# Relay.net
KiCad netlist of a schematic drawn in Altium Designer
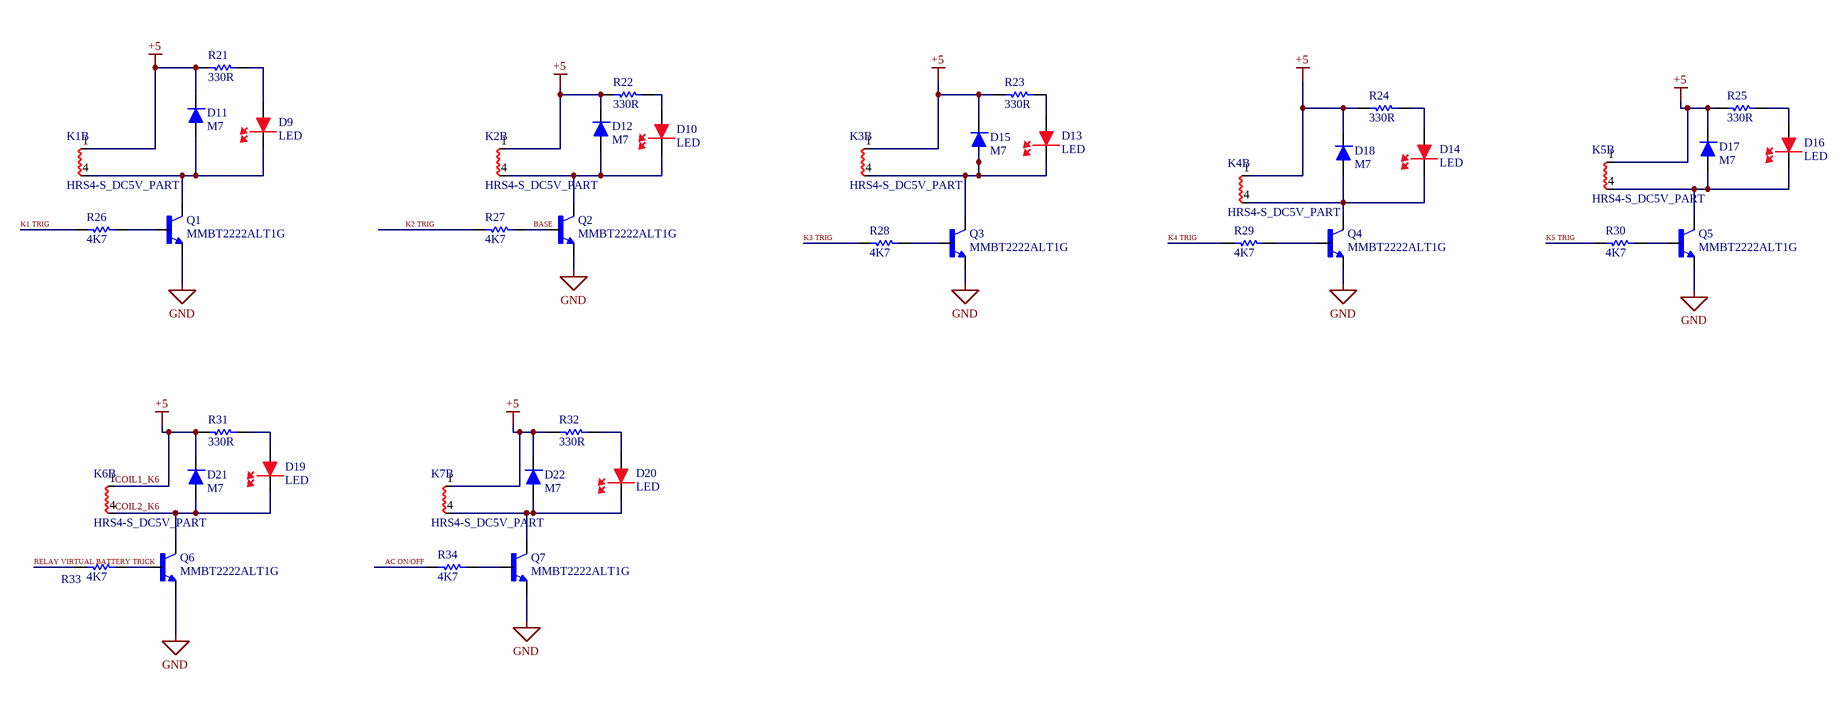
[diagram p0: Relay.SchDoc]

(export (version "E")
  (design (tool "Eeschema 10.0.6"))
  (components
    (comp (ref "D9")
      (value "LED")
      (footprint "0805 (1205) LED")
      (description "LED SMD  mcd,Red Color Red Diffused Lens")
      (libsource (lib "PCB_Project_1") (part "LED RED (SMD)"))
    )
    (comp (ref "D10")
      (value "LED")
      (footprint "0805 (1205) LED")
      (description "LED SMD  mcd,Red Color Red Diffused Lens")
      (libsource (lib "PCB_Project_1") (part "LED RED (SMD)"))
    )
    (comp (ref "D11")
      (value "M7")
      (footprint "DO-214AC")
      (description "M7 Rectifier Diode 1000V/1A . Package  DO-214AC (SMA)")
      (fields (field (name "PUBLISHER") "Altium Limited"))
      (libsource (lib "PCB_Project_1") (part "Diode M7"))
    )
    (comp (ref "D12")
      (value "M7")
      (footprint "DO-214AC")
      (description "M7 Rectifier Diode 1000V/1A . Package  DO-214AC (SMA)")
      (fields (field (name "PUBLISHER") "Altium Limited"))
      (libsource (lib "PCB_Project_1") (part "Diode M7"))
    )
    (comp (ref "D13")
      (value "LED")
      (footprint "0805 (1205) LED")
      (description "LED SMD  mcd,Red Color Red Diffused Lens")
      (libsource (lib "PCB_Project_1") (part "LED RED (SMD)"))
    )
    (comp (ref "D14")
      (value "LED")
      (footprint "0805 (1205) LED")
      (description "LED SMD  mcd,Red Color Red Diffused Lens")
      (libsource (lib "PCB_Project_1") (part "LED RED (SMD)"))
    )
    (comp (ref "D15")
      (value "M7")
      (footprint "DO-214AC")
      (description "M7 Rectifier Diode 1000V/1A . Package  DO-214AC (SMA)")
      (fields (field (name "PUBLISHER") "Altium Limited"))
      (libsource (lib "PCB_Project_1") (part "Diode M7"))
    )
    (comp (ref "D16")
      (value "LED")
      (footprint "0805 (1205) LED")
      (description "LED SMD  mcd,Red Color Red Diffused Lens")
      (libsource (lib "PCB_Project_1") (part "LED RED (SMD)"))
    )
    (comp (ref "D17")
      (value "M7")
      (footprint "DO-214AC")
      (description "M7 Rectifier Diode 1000V/1A . Package  DO-214AC (SMA)")
      (fields (field (name "PUBLISHER") "Altium Limited"))
      (libsource (lib "PCB_Project_1") (part "Diode M7"))
    )
    (comp (ref "D18")
      (value "M7")
      (footprint "DO-214AC")
      (description "M7 Rectifier Diode 1000V/1A . Package  DO-214AC (SMA)")
      (fields (field (name "PUBLISHER") "Altium Limited"))
      (libsource (lib "PCB_Project_1") (part "Diode M7"))
    )
    (comp (ref "D19")
      (value "LED")
      (footprint "0805 (1205) LED")
      (description "LED SMD  mcd,Red Color Red Diffused Lens")
      (libsource (lib "PCB_Project_1") (part "LED RED (SMD)"))
    )
    (comp (ref "D20")
      (value "LED")
      (footprint "0805 (1205) LED")
      (description "LED SMD  mcd,Red Color Red Diffused Lens")
      (libsource (lib "PCB_Project_1") (part "LED RED (SMD)"))
    )
    (comp (ref "D21")
      (value "M7")
      (footprint "DO-214AC")
      (description "M7 Rectifier Diode 1000V/1A . Package  DO-214AC (SMA)")
      (fields (field (name "PUBLISHER") "Altium Limited"))
      (libsource (lib "PCB_Project_1") (part "Diode M7"))
    )
    (comp (ref "D22")
      (value "M7")
      (footprint "DO-214AC")
      (description "M7 Rectifier Diode 1000V/1A . Package  DO-214AC (SMA)")
      (fields (field (name "PUBLISHER") "Altium Limited"))
      (libsource (lib "PCB_Project_1") (part "Diode M7"))
    )
    (comp (ref "K1")
      (value "HRS4-S_DC5V_PART")
      (footprint "SamacSys:HRS4SDC5V")
      (description "Relay or Contactor")
      (fields (field (name "MANUFACTURER_PART_NUMBER") "HRS4-S DC5V"))
      (libsource (lib "SamacSys") (part "HRS4-S_DC5V_PART"))
    )
    (comp (ref "K2")
      (value "HRS4-S_DC5V_PART")
      (footprint "SamacSys:HRS4SDC5V")
      (description "Relay or Contactor")
      (fields (field (name "MANUFACTURER_PART_NUMBER") "HRS4-S DC5V"))
      (libsource (lib "SamacSys") (part "HRS4-S_DC5V_PART"))
    )
    (comp (ref "K3")
      (value "HRS4-S_DC5V_PART")
      (footprint "SamacSys:HRS4SDC5V")
      (description "Relay or Contactor")
      (fields (field (name "MANUFACTURER_PART_NUMBER") "HRS4-S DC5V"))
      (libsource (lib "SamacSys") (part "HRS4-S_DC5V_PART"))
    )
    (comp (ref "K4")
      (value "HRS4-S_DC5V_PART")
      (footprint "SamacSys:HRS4SDC5V")
      (description "Relay or Contactor")
      (fields (field (name "MANUFACTURER_PART_NUMBER") "HRS4-S DC5V"))
      (libsource (lib "SamacSys") (part "HRS4-S_DC5V_PART"))
    )
    (comp (ref "K5")
      (value "HRS4-S_DC5V_PART")
      (footprint "SamacSys:HRS4SDC5V")
      (description "Relay or Contactor")
      (fields (field (name "MANUFACTURER_PART_NUMBER") "HRS4-S DC5V"))
      (libsource (lib "SamacSys") (part "HRS4-S_DC5V_PART"))
    )
    (comp (ref "K6")
      (value "HRS4-S_DC5V_PART")
      (footprint "SamacSys:HRS4SDC5V")
      (description "Relay or Contactor")
      (fields (field (name "MANUFACTURER_PART_NUMBER") "HRS4-S DC5V"))
      (libsource (lib "SamacSys") (part "HRS4-S_DC5V_PART"))
    )
    (comp (ref "K7")
      (value "HRS4-S_DC5V_PART")
      (footprint "SamacSys:HRS4SDC5V")
      (description "Relay or Contactor")
      (fields (field (name "MANUFACTURER_PART_NUMBER") "HRS4-S DC5V"))
      (libsource (lib "SamacSys") (part "HRS4-S_DC5V_PART"))
    )
    (comp (ref "Q1")
      (value "MMBT2222ALT1G")
      (footprint "SOT95P237X111-3N")
      (description "Bipolar (BJT) Transistor NPN 40 V 600 mA 300MHz 225 mW Surface Mount SOT-23-3 (TO-236)")
      (fields (field (name "MF") "ON Semiconductor"))
      (libsource (lib "PCB_Project_1") (part "MMBT2222ALT1G"))
    )
    (comp (ref "Q2")
      (value "MMBT2222ALT1G")
      (footprint "SOT95P237X111-3N")
      (description "Bipolar (BJT) Transistor NPN 40 V 600 mA 300MHz 225 mW Surface Mount SOT-23-3 (TO-236)")
      (fields (field (name "MF") "ON Semiconductor"))
      (libsource (lib "PCB_Project_1") (part "MMBT2222ALT1G"))
    )
    (comp (ref "Q3")
      (value "MMBT2222ALT1G")
      (footprint "SOT95P237X111-3N")
      (description "Bipolar (BJT) Transistor NPN 40 V 600 mA 300MHz 225 mW Surface Mount SOT-23-3 (TO-236)")
      (fields (field (name "MF") "ON Semiconductor"))
      (libsource (lib "PCB_Project_1") (part "MMBT2222ALT1G"))
    )
    (comp (ref "Q4")
      (value "MMBT2222ALT1G")
      (footprint "SOT95P237X111-3N")
      (description "Bipolar (BJT) Transistor NPN 40 V 600 mA 300MHz 225 mW Surface Mount SOT-23-3 (TO-236)")
      (fields (field (name "MF") "ON Semiconductor"))
      (libsource (lib "PCB_Project_1") (part "MMBT2222ALT1G"))
    )
    (comp (ref "Q5")
      (value "MMBT2222ALT1G")
      (footprint "SOT95P237X111-3N")
      (description "Bipolar (BJT) Transistor NPN 40 V 600 mA 300MHz 225 mW Surface Mount SOT-23-3 (TO-236)")
      (fields (field (name "MF") "ON Semiconductor"))
      (libsource (lib "PCB_Project_1") (part "MMBT2222ALT1G"))
    )
    (comp (ref "Q6")
      (value "MMBT2222ALT1G")
      (footprint "SOT95P237X111-3N")
      (description "Bipolar (BJT) Transistor NPN 40 V 600 mA 300MHz 225 mW Surface Mount SOT-23-3 (TO-236)")
      (fields (field (name "MF") "ON Semiconductor"))
      (libsource (lib "PCB_Project_1") (part "MMBT2222ALT1G"))
    )
    (comp (ref "Q7")
      (value "MMBT2222ALT1G")
      (footprint "SOT95P237X111-3N")
      (description "Bipolar (BJT) Transistor NPN 40 V 600 mA 300MHz 225 mW Surface Mount SOT-23-3 (TO-236)")
      (fields (field (name "MF") "ON Semiconductor"))
      (libsource (lib "PCB_Project_1") (part "MMBT2222ALT1G"))
    )
    (comp (ref "R21")
      (value "330R")
      (footprint "0805 Modificado")
      (description "'RES SMD 330 OHM 5% 1/8W 0805/0805W8F3300T5E")
      (libsource (lib "MCU POWER BOARD") (part "Resistor SMD 330R +/- 1% (CHIP)"))
    )
    (comp (ref "R22")
      (value "330R")
      (footprint "0805 Modificado")
      (description "'RES SMD 330 OHM 5% 1/8W 0805/0805W8F3300T5E")
      (libsource (lib "MCU POWER BOARD") (part "Resistor SMD 330R +/- 1% (CHIP)"))
    )
    (comp (ref "R23")
      (value "330R")
      (footprint "0805 Modificado")
      (description "'RES SMD 330 OHM 5% 1/8W 0805/0805W8F3300T5E")
      (libsource (lib "MCU POWER BOARD") (part "Resistor SMD 330R +/- 1% (CHIP)"))
    )
    (comp (ref "R24")
      (value "330R")
      (footprint "0805 Modificado")
      (description "'RES SMD 330 OHM 5% 1/8W 0805/0805W8F3300T5E")
      (libsource (lib "MCU POWER BOARD") (part "Resistor SMD 330R +/- 1% (CHIP)"))
    )
    (comp (ref "R25")
      (value "330R")
      (footprint "0805 Modificado")
      (description "'RES SMD 330 OHM 5% 1/8W 0805/0805W8F3300T5E")
      (libsource (lib "MCU POWER BOARD") (part "Resistor SMD 330R +/- 1% (CHIP)"))
    )
    (comp (ref "R26")
      (value "4K7")
      (footprint "0805 Modificado")
      (description "'RES SMD 330 OHM 5% 1/8W 0805/0805W8F3300T5E")
      (libsource (lib "MCU POWER BOARD") (part "Resistor SMD 330R +/- 1% (CHIP)"))
    )
    (comp (ref "R27")
      (value "4K7")
      (footprint "0805 Modificado")
      (description "'RES SMD 330 OHM 5% 1/8W 0805/0805W8F3300T5E")
      (libsource (lib "MCU POWER BOARD") (part "Resistor SMD 330R +/- 1% (CHIP)"))
    )
    (comp (ref "R28")
      (value "4K7")
      (footprint "0805 Modificado")
      (description "'RES SMD 330 OHM 5% 1/8W 0805/0805W8F3300T5E")
      (libsource (lib "MCU POWER BOARD") (part "Resistor SMD 330R +/- 1% (CHIP)"))
    )
    (comp (ref "R29")
      (value "4K7")
      (footprint "0805 Modificado")
      (description "'RES SMD 330 OHM 5% 1/8W 0805/0805W8F3300T5E")
      (libsource (lib "MCU POWER BOARD") (part "Resistor SMD 330R +/- 1% (CHIP)"))
    )
    (comp (ref "R30")
      (value "4K7")
      (footprint "0805 Modificado")
      (description "'RES SMD 330 OHM 5% 1/8W 0805/0805W8F3300T5E")
      (libsource (lib "MCU POWER BOARD") (part "Resistor SMD 330R +/- 1% (CHIP)"))
    )
    (comp (ref "R31")
      (value "330R")
      (footprint "0805 Modificado")
      (description "'RES SMD 330 OHM 5% 1/8W 0805/0805W8F3300T5E")
      (libsource (lib "MCU POWER BOARD") (part "Resistor SMD 330R +/- 1% (CHIP)"))
    )
    (comp (ref "R32")
      (value "330R")
      (footprint "0805 Modificado")
      (description "'RES SMD 330 OHM 5% 1/8W 0805/0805W8F3300T5E")
      (libsource (lib "MCU POWER BOARD") (part "Resistor SMD 330R +/- 1% (CHIP)"))
    )
    (comp (ref "R33")
      (value "4K7")
      (footprint "0805 Modificado")
      (description "'RES SMD 4700 OHM 5% 1/8W 0805/0805W8F3300T5E")
      (libsource (lib "MCU POWER BOARD") (part "Resistor SMD 330R +/- 1% (CHIP)"))
    )
    (comp (ref "R34")
      (value "4K7")
      (footprint "0805 Modificado")
      (description "'RES SMD 4K7 5% 1/8W 0805/0805W8F3300T5E")
      (libsource (lib "MCU POWER BOARD") (part "Resistor SMD 330R +/- 1% (CHIP)"))
    )
  )
  (nets
    (net (code "1") (name "+5") (class "Default")
      (node (ref "D11") (pin "K") (pinfunction "K_K") (pintype "passive"))
      (node (ref "D12") (pin "K") (pinfunction "K_K") (pintype "passive"))
      (node (ref "D15") (pin "K") (pinfunction "K_K") (pintype "passive"))
      (node (ref "D17") (pin "K") (pinfunction "K_K") (pintype "passive"))
      (node (ref "D18") (pin "K") (pinfunction "K_K") (pintype "passive"))
      (node (ref "D21") (pin "K") (pinfunction "K_K") (pintype "passive"))
      (node (ref "D22") (pin "K") (pinfunction "K_K") (pintype "passive"))
      (node (ref "K1") (pin "1") (pinfunction "COIL_1_1") (pintype "passive"))
      (node (ref "K2") (pin "1") (pinfunction "COIL_1_1") (pintype "passive"))
      (node (ref "K3") (pin "1") (pinfunction "COIL_1_1") (pintype "passive"))
      (node (ref "K4") (pin "1") (pinfunction "COIL_1_1") (pintype "passive"))
      (node (ref "K5") (pin "1") (pinfunction "COIL_1_1") (pintype "passive"))
      (node (ref "K6") (pin "1") (pinfunction "COIL_1_1") (pintype "passive"))
      (node (ref "K7") (pin "1") (pinfunction "COIL_1_1") (pintype "passive"))
      (node (ref "R21") (pin "2") (pinfunction "2_2") (pintype "passive"))
      (node (ref "R22") (pin "2") (pinfunction "2_2") (pintype "passive"))
      (node (ref "R23") (pin "2") (pinfunction "2_2") (pintype "passive"))
      (node (ref "R24") (pin "2") (pinfunction "2_2") (pintype "passive"))
      (node (ref "R25") (pin "2") (pinfunction "2_2") (pintype "passive"))
      (node (ref "R31") (pin "2") (pinfunction "2_2") (pintype "passive"))
      (node (ref "R32") (pin "2") (pinfunction "2_2") (pintype "passive"))
    )
    (net (code "2") (name "/AC ON{slash}OFF") (class "Default")
      (node (ref "R34") (pin "2") (pinfunction "2_2") (pintype "passive"))
    )
    (net (code "3") (name "/BASE") (class "Default")
      (node (ref "Q2") (pin "1") (pinfunction "B_1") (pintype "passive"))
      (node (ref "R27") (pin "1") (pinfunction "1_1") (pintype "passive"))
    )
    (net (code "4") (name "/COIL2_K6") (class "Default")
      (node (ref "D19") (pin "1") (pinfunction "K_1") (pintype "passive"))
      (node (ref "D21") (pin "A") (pinfunction "A_A") (pintype "passive"))
      (node (ref "K6") (pin "4") (pinfunction "COIL_2_4") (pintype "passive"))
      (node (ref "Q6") (pin "3") (pinfunction "C_3") (pintype "passive"))
    )
    (net (code "5") (name "/K1 TRIG") (class "Default")
      (node (ref "R26") (pin "2") (pinfunction "2_2") (pintype "passive"))
    )
    (net (code "6") (name "/K2 TRIG") (class "Default")
      (node (ref "R27") (pin "2") (pinfunction "2_2") (pintype "passive"))
    )
    (net (code "7") (name "/K3 TRIG") (class "Default")
      (node (ref "R28") (pin "2") (pinfunction "2_2") (pintype "passive"))
    )
    (net (code "8") (name "/K4 TRIG") (class "Default")
      (node (ref "R29") (pin "2") (pinfunction "2_2") (pintype "passive"))
    )
    (net (code "9") (name "/K5 TRIG") (class "Default")
      (node (ref "R30") (pin "2") (pinfunction "2_2") (pintype "passive"))
    )
    (net (code "10") (name "/RELAY VIRTUAL BATTERY TRICK") (class "Default")
      (node (ref "R33") (pin "2") (pinfunction "2_2") (pintype "passive"))
    )
    (net (code "11") (name "GND") (class "Default")
      (node (ref "Q1") (pin "2") (pinfunction "E_2") (pintype "passive"))
      (node (ref "Q2") (pin "2") (pinfunction "E_2") (pintype "passive"))
      (node (ref "Q3") (pin "2") (pinfunction "E_2") (pintype "passive"))
      (node (ref "Q4") (pin "2") (pinfunction "E_2") (pintype "passive"))
      (node (ref "Q5") (pin "2") (pinfunction "E_2") (pintype "passive"))
      (node (ref "Q6") (pin "2") (pinfunction "E_2") (pintype "passive"))
      (node (ref "Q7") (pin "2") (pinfunction "E_2") (pintype "passive"))
    )
    (net (code "12") (name "Net-(D9-A)") (class "Default")
      (node (ref "D9") (pin "2") (pinfunction "A_2") (pintype "passive"))
      (node (ref "R21") (pin "1") (pinfunction "1_1") (pintype "passive"))
    )
    (net (code "13") (name "Net-(D9-K)") (class "Default")
      (node (ref "D11") (pin "A") (pinfunction "A_A") (pintype "passive"))
      (node (ref "D9") (pin "1") (pinfunction "K_1") (pintype "passive"))
      (node (ref "K1") (pin "4") (pinfunction "COIL_2_4") (pintype "passive"))
      (node (ref "Q1") (pin "3") (pinfunction "C_3") (pintype "passive"))
    )
    (net (code "14") (name "Net-(D10-A)") (class "Default")
      (node (ref "D10") (pin "2") (pinfunction "A_2") (pintype "passive"))
      (node (ref "R22") (pin "1") (pinfunction "1_1") (pintype "passive"))
    )
    (net (code "15") (name "Net-(D10-K)") (class "Default")
      (node (ref "D10") (pin "1") (pinfunction "K_1") (pintype "passive"))
      (node (ref "D12") (pin "A") (pinfunction "A_A") (pintype "passive"))
      (node (ref "K2") (pin "4") (pinfunction "COIL_2_4") (pintype "passive"))
      (node (ref "Q2") (pin "3") (pinfunction "C_3") (pintype "passive"))
    )
    (net (code "16") (name "Net-(D13-A)") (class "Default")
      (node (ref "D13") (pin "2") (pinfunction "A_2") (pintype "passive"))
      (node (ref "R23") (pin "1") (pinfunction "1_1") (pintype "passive"))
    )
    (net (code "17") (name "Net-(D13-K)") (class "Default")
      (node (ref "D13") (pin "1") (pinfunction "K_1") (pintype "passive"))
      (node (ref "D15") (pin "A") (pinfunction "A_A") (pintype "passive"))
      (node (ref "K3") (pin "4") (pinfunction "COIL_2_4") (pintype "passive"))
      (node (ref "Q3") (pin "3") (pinfunction "C_3") (pintype "passive"))
    )
    (net (code "18") (name "Net-(D14-A)") (class "Default")
      (node (ref "D14") (pin "2") (pinfunction "A_2") (pintype "passive"))
      (node (ref "R24") (pin "1") (pinfunction "1_1") (pintype "passive"))
    )
    (net (code "19") (name "Net-(D14-K)") (class "Default")
      (node (ref "D14") (pin "1") (pinfunction "K_1") (pintype "passive"))
      (node (ref "D18") (pin "A") (pinfunction "A_A") (pintype "passive"))
      (node (ref "K4") (pin "4") (pinfunction "COIL_2_4") (pintype "passive"))
      (node (ref "Q4") (pin "3") (pinfunction "C_3") (pintype "passive"))
    )
    (net (code "20") (name "Net-(D16-A)") (class "Default")
      (node (ref "D16") (pin "2") (pinfunction "A_2") (pintype "passive"))
      (node (ref "R25") (pin "1") (pinfunction "1_1") (pintype "passive"))
    )
    (net (code "21") (name "Net-(D16-K)") (class "Default")
      (node (ref "D16") (pin "1") (pinfunction "K_1") (pintype "passive"))
      (node (ref "D17") (pin "A") (pinfunction "A_A") (pintype "passive"))
      (node (ref "K5") (pin "4") (pinfunction "COIL_2_4") (pintype "passive"))
      (node (ref "Q5") (pin "3") (pinfunction "C_3") (pintype "passive"))
    )
    (net (code "22") (name "Net-(D19-A)") (class "Default")
      (node (ref "D19") (pin "2") (pinfunction "A_2") (pintype "passive"))
      (node (ref "R31") (pin "1") (pinfunction "1_1") (pintype "passive"))
    )
    (net (code "23") (name "Net-(D20-A)") (class "Default")
      (node (ref "D20") (pin "2") (pinfunction "A_2") (pintype "passive"))
      (node (ref "R32") (pin "1") (pinfunction "1_1") (pintype "passive"))
    )
    (net (code "24") (name "Net-(D20-K)") (class "Default")
      (node (ref "D20") (pin "1") (pinfunction "K_1") (pintype "passive"))
      (node (ref "D22") (pin "A") (pinfunction "A_A") (pintype "passive"))
      (node (ref "K7") (pin "4") (pinfunction "COIL_2_4") (pintype "passive"))
      (node (ref "Q7") (pin "3") (pinfunction "C_3") (pintype "passive"))
    )
    (net (code "25") (name "Net-(Q1-B)") (class "Default")
      (node (ref "Q1") (pin "1") (pinfunction "B_1") (pintype "passive"))
      (node (ref "R26") (pin "1") (pinfunction "1_1") (pintype "passive"))
    )
    (net (code "26") (name "Net-(Q3-B)") (class "Default")
      (node (ref "Q3") (pin "1") (pinfunction "B_1") (pintype "passive"))
      (node (ref "R28") (pin "1") (pinfunction "1_1") (pintype "passive"))
    )
    (net (code "27") (name "Net-(Q4-B)") (class "Default")
      (node (ref "Q4") (pin "1") (pinfunction "B_1") (pintype "passive"))
      (node (ref "R29") (pin "1") (pinfunction "1_1") (pintype "passive"))
    )
    (net (code "28") (name "Net-(Q5-B)") (class "Default")
      (node (ref "Q5") (pin "1") (pinfunction "B_1") (pintype "passive"))
      (node (ref "R30") (pin "1") (pinfunction "1_1") (pintype "passive"))
    )
    (net (code "29") (name "Net-(Q6-B)") (class "Default")
      (node (ref "Q6") (pin "1") (pinfunction "B_1") (pintype "passive"))
      (node (ref "R33") (pin "1") (pinfunction "1_1") (pintype "passive"))
    )
    (net (code "30") (name "Net-(Q7-B)") (class "Default")
      (node (ref "Q7") (pin "1") (pinfunction "B_1") (pintype "passive"))
      (node (ref "R34") (pin "1") (pinfunction "1_1") (pintype "passive"))
    )
  )
)
